# Integrated_Main_Driver_Board-04-Debug_Co.net
KiCad netlist of a schematic drawn in Altium Designer
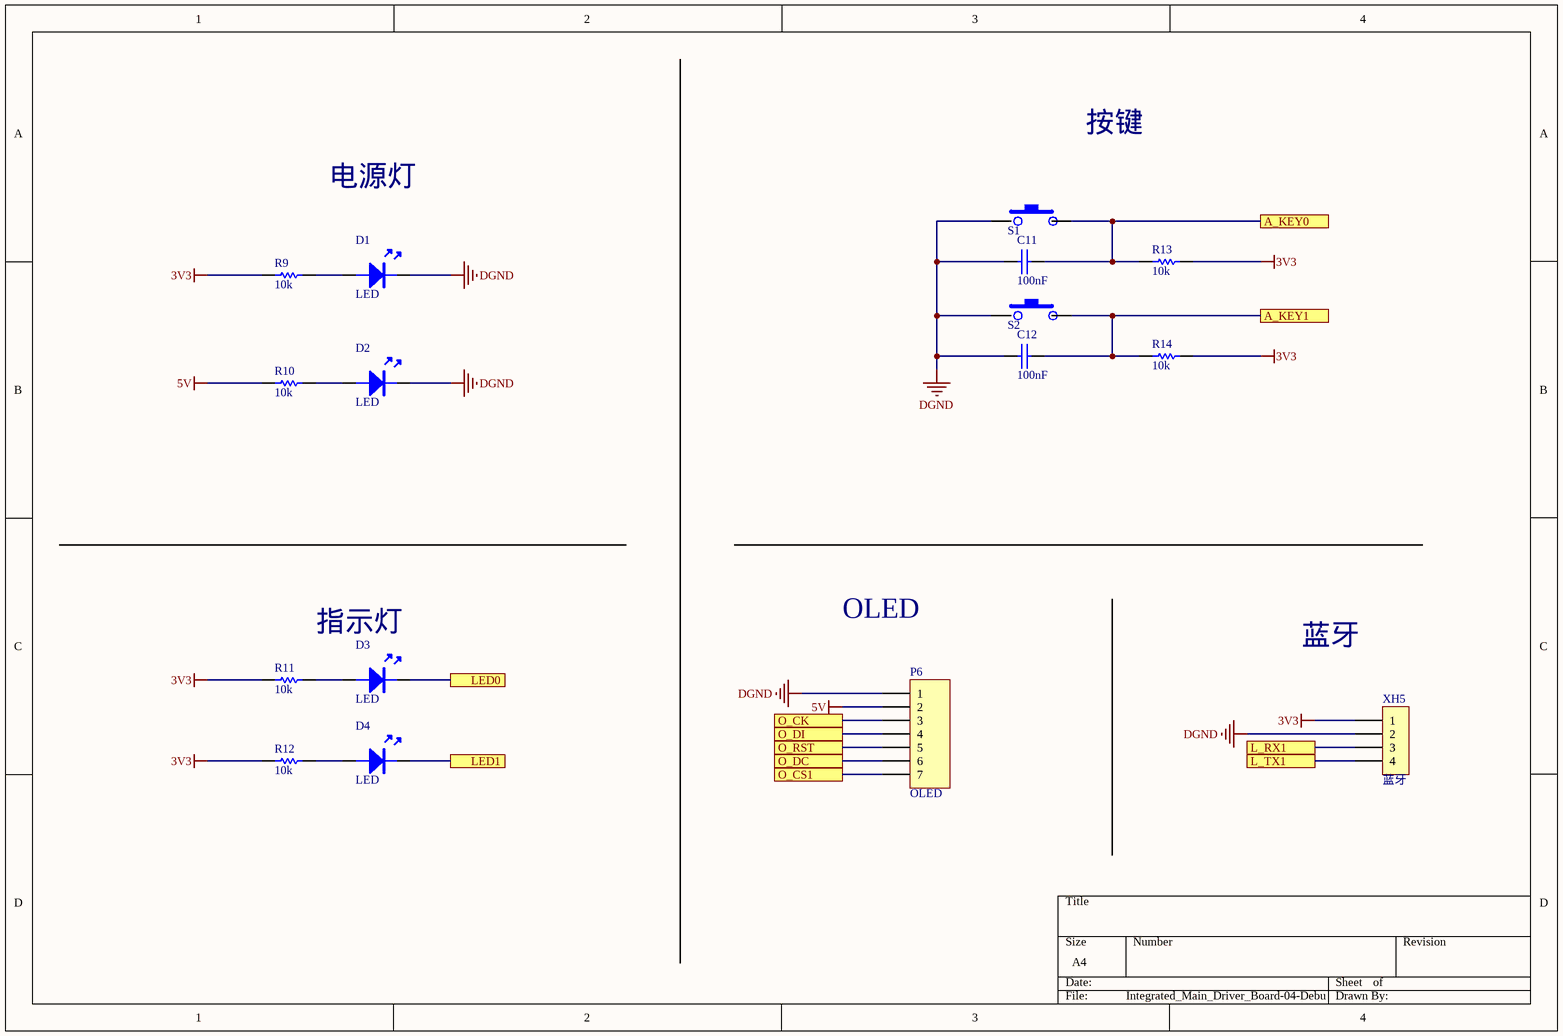
[diagram p0: Integrated_Main_Driver_Board-04-Debug & Communication Circuit-20230110.SchDoc]

(export (version "E")
  (design (tool "Eeschema 10.0.6"))
  (components
    (comp (ref "C11") (value "100nF") (footprint "0402C") (libsource (lib "电容") (part "CAP")))
    (comp (ref "C12") (value "100nF") (footprint "0402C") (libsource (lib "电容") (part "CAP")))
    (comp (ref "D1") (value "LED") (footprint "LED-0603B") (libsource (lib "LED") (part "LED")))
    (comp (ref "D2") (value "LED") (footprint "LED-0603B") (libsource (lib "LED") (part "LED")))
    (comp (ref "D3") (value "LED") (footprint "LED-0603B") (libsource (lib "LED") (part "LED")))
    (comp (ref "D4") (value "LED") (footprint "LED-0603B") (libsource (lib "LED") (part "LED")))
    (comp (ref "P6")
      (value "OLED")
      (footprint "HDR1X7")
      (description "Header, 7-Pin")
      (fields (field (name "PUBLISHER") "Altium Limited"))
      (libsource (lib "Miscellaneous Connectors") (part "Header 7"))
    )
    (comp (ref "R9") (value "10k") (footprint "0402R") (libsource (lib "电阻") (part "RES")))
    (comp (ref "R10") (value "10k") (footprint "0402R") (libsource (lib "电阻") (part "RES")))
    (comp (ref "R11") (value "10k") (footprint "0402R") (libsource (lib "电阻") (part "RES")))
    (comp (ref "R12") (value "10k") (footprint "0402R") (libsource (lib "电阻") (part "RES")))
    (comp (ref "R13") (value "10k") (footprint "0402R") (libsource (lib "电阻") (part "RES")))
    (comp (ref "R14") (value "10k") (footprint "0402R") (libsource (lib "电阻") (part "RES")))
    (comp (ref "S1")
      (value "轻触开关（3*6*2.5mm）")
      (footprint "轻触开关（3*6*2.5mm）")
      (libsource (lib "主控板库") (part "轻触开关 3*6*2.5mm"))
    )
    (comp (ref "S2")
      (value "轻触开关（3*6*2.5mm）")
      (footprint "轻触开关（3*6*2.5mm）")
      (libsource (lib "主控板库") (part "轻触开关 3*6*2.5mm"))
    )
    (comp (ref "XH5") (value "蓝牙") (footprint "XH4/2.54mm/180") (libsource (lib "XH，VH") (part "XH4")))
  )
  (nets
    (net (code "1") (name "/A_KEY0") (class "Default")
      (node (ref "C11") (pin "1") (pinfunction "1_1") (pintype "passive"))
      (node (ref "R13") (pin "1") (pinfunction "1_1") (pintype "passive"))
      (node (ref "S1") (pin "2") (pinfunction "2_2") (pintype "passive"))
    )
    (net (code "2") (name "/A_KEY1") (class "Default")
      (node (ref "C12") (pin "1") (pinfunction "1_1") (pintype "passive"))
      (node (ref "R14") (pin "1") (pinfunction "1_1") (pintype "passive"))
      (node (ref "S2") (pin "2") (pinfunction "2_2") (pintype "passive"))
    )
    (net (code "3") (name "/LED0") (class "Default")
      (node (ref "D3") (pin "K") (pinfunction "K_K") (pintype "passive"))
    )
    (net (code "4") (name "/LED1") (class "Default")
      (node (ref "D4") (pin "K") (pinfunction "K_K") (pintype "passive"))
    )
    (net (code "5") (name "/L_RX1") (class "Default")
      (node (ref "XH5") (pin "3") (pinfunction "3_3") (pintype "passive"))
    )
    (net (code "6") (name "/L_TX1") (class "Default")
      (node (ref "XH5") (pin "4") (pinfunction "4_4") (pintype "passive"))
    )
    (net (code "7") (name "/O_CK") (class "Default")
      (node (ref "P6") (pin "3") (pinfunction "3_3") (pintype "passive"))
    )
    (net (code "8") (name "/O_CS1") (class "Default")
      (node (ref "P6") (pin "7") (pinfunction "7_7") (pintype "passive"))
    )
    (net (code "9") (name "/O_DC") (class "Default")
      (node (ref "P6") (pin "6") (pinfunction "6_6") (pintype "passive"))
    )
    (net (code "10") (name "/O_DI") (class "Default")
      (node (ref "P6") (pin "4") (pinfunction "4_4") (pintype "passive"))
    )
    (net (code "11") (name "/O_RST") (class "Default")
      (node (ref "P6") (pin "5") (pinfunction "5_5") (pintype "passive"))
    )
    (net (code "12") (name "3V3") (class "Default")
      (node (ref "R11") (pin "1") (pinfunction "1_1") (pintype "passive"))
      (node (ref "R12") (pin "1") (pinfunction "1_1") (pintype "passive"))
      (node (ref "R13") (pin "2") (pinfunction "2_2") (pintype "passive"))
      (node (ref "R14") (pin "2") (pinfunction "2_2") (pintype "passive"))
      (node (ref "R9") (pin "1") (pinfunction "1_1") (pintype "passive"))
      (node (ref "XH5") (pin "1") (pinfunction "1_1") (pintype "passive"))
    )
    (net (code "13") (name "5V") (class "Default")
      (node (ref "P6") (pin "2") (pinfunction "2_2") (pintype "passive"))
      (node (ref "R10") (pin "1") (pinfunction "1_1") (pintype "passive"))
    )
    (net (code "14") (name "DGND") (class "Default")
      (node (ref "C11") (pin "2") (pinfunction "2_2") (pintype "passive"))
      (node (ref "C12") (pin "2") (pinfunction "2_2") (pintype "passive"))
      (node (ref "D1") (pin "K") (pinfunction "K_K") (pintype "passive"))
      (node (ref "D2") (pin "K") (pinfunction "K_K") (pintype "passive"))
      (node (ref "P6") (pin "1") (pinfunction "1_1") (pintype "passive"))
      (node (ref "S1") (pin "1") (pinfunction "1_1") (pintype "passive"))
      (node (ref "S2") (pin "1") (pinfunction "1_1") (pintype "passive"))
      (node (ref "XH5") (pin "2") (pinfunction "2_2") (pintype "passive"))
    )
    (net (code "15") (name "Net-(D1-PadA)") (class "Default")
      (node (ref "D1") (pin "A") (pinfunction "A_A") (pintype "passive"))
      (node (ref "R9") (pin "2") (pinfunction "2_2") (pintype "passive"))
    )
    (net (code "16") (name "Net-(D2-PadA)") (class "Default")
      (node (ref "D2") (pin "A") (pinfunction "A_A") (pintype "passive"))
      (node (ref "R10") (pin "2") (pinfunction "2_2") (pintype "passive"))
    )
    (net (code "17") (name "Net-(D3-PadA)") (class "Default")
      (node (ref "D3") (pin "A") (pinfunction "A_A") (pintype "passive"))
      (node (ref "R11") (pin "2") (pinfunction "2_2") (pintype "passive"))
    )
    (net (code "18") (name "Net-(D4-PadA)") (class "Default")
      (node (ref "D4") (pin "A") (pinfunction "A_A") (pintype "passive"))
      (node (ref "R12") (pin "2") (pinfunction "2_2") (pintype "passive"))
    )
  )
)
